# Voltage_regulator_board.net
KiCad netlist of a schematic drawn in EAGLE
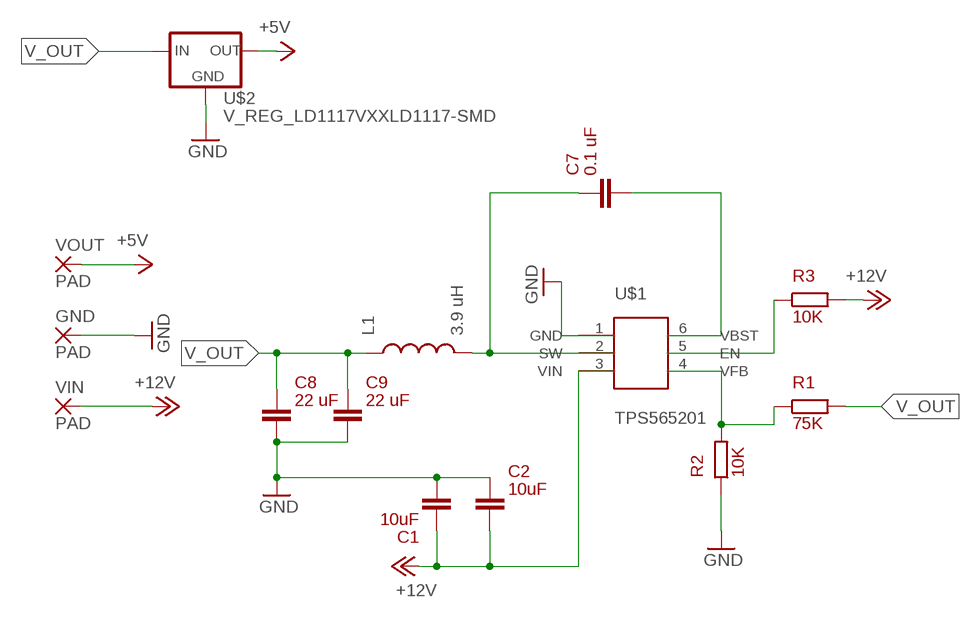
[diagram p0: schematic, sheet 1]

(export (version "E")
  (design (tool "Eeschema 10.0.6"))
  (components
    (comp (ref "C1")
      (value "10uF")
      (footprint "eagle-import:C1206K")
      (libsource (lib "eagle-import") (part "1206CAPACITOR"))
    )
    (comp (ref "C2")
      (value "10uF")
      (footprint "eagle-import:C1206K")
      (libsource (lib "eagle-import") (part "1206CAPACITOR"))
    )
    (comp (ref "C7")
      (value "0.1 uF")
      (footprint "eagle-import:C1206K")
      (libsource (lib "eagle-import") (part "1206CAPACITOR"))
    )
    (comp (ref "C8")
      (value "22 uF")
      (footprint "eagle-import:C1206K")
      (libsource (lib "eagle-import") (part "1206CAPACITOR"))
    )
    (comp (ref "C9")
      (value "22 uF")
      (footprint "eagle-import:C1206K")
      (libsource (lib "eagle-import") (part "1206CAPACITOR"))
    )
    (comp (ref "GND")
      (value "PAD")
      (footprint "eagle-import:PAD")
      (libsource (lib "eagle-import") (part "PAD"))
    )
    (comp (ref "L1")
      (value "3.9 uH")
      (footprint "eagle-import:SRN6028")
      (libsource (lib "eagle-import") (part "SRN6028"))
    )
    (comp (ref "R1")
      (value "75K")
      (footprint "eagle-import:C0603K")
      (libsource (lib "eagle-import") (part "0603RESISTOR"))
    )
    (comp (ref "R2")
      (value "10K")
      (footprint "eagle-import:C0603K")
      (libsource (lib "eagle-import") (part "0603RESISTOR"))
    )
    (comp (ref "R3")
      (value "10K")
      (footprint "eagle-import:C0603K")
      (libsource (lib "eagle-import") (part "0603RESISTOR"))
    )
    (comp (ref "U$1")
      (value "TPS565201")
      (footprint "eagle-import:SOT23-6")
      (libsource (lib "eagle-import") (part "TPS565201"))
    )
    (comp (ref "U$2")
      (value "V_REG_LD1117VXXLD1117-SMD")
      (footprint "eagle-import:SOT223")
      (libsource (lib "eagle-import") (part "V_REG_LD1117VXXLD1117-SMD"))
    )
    (comp (ref "VIN")
      (value "PAD")
      (footprint "eagle-import:PAD")
      (libsource (lib "eagle-import") (part "PAD"))
    )
    (comp (ref "VOUT")
      (value "PAD")
      (footprint "eagle-import:PAD")
      (libsource (lib "eagle-import") (part "PAD"))
    )
  )
  (nets
    (net (code "1") (name "+5V") (class "Default")
      (node (ref "U$2") (pin "2") (pinfunction "OUT_2") (pintype "passive"))
      (node (ref "VOUT") (pin "1") (pinfunction "P_1") (pintype "passive"))
    )
    (net (code "2") (name "+12V") (class "Default")
      (node (ref "C1") (pin "1") (pinfunction "1_1") (pintype "passive"))
      (node (ref "C2") (pin "2") (pinfunction "2_2") (pintype "passive"))
      (node (ref "R3") (pin "2") (pinfunction "2_2") (pintype "passive"))
      (node (ref "U$1") (pin "3") (pinfunction "VIN_3") (pintype "bidirectional"))
      (node (ref "VIN") (pin "1") (pinfunction "P_1") (pintype "passive"))
    )
    (net (code "3") (name "GND") (class "Default")
      (node (ref "C1") (pin "2") (pinfunction "2_2") (pintype "passive"))
      (node (ref "C2") (pin "1") (pinfunction "1_1") (pintype "passive"))
      (node (ref "C8") (pin "2") (pinfunction "2_2") (pintype "passive"))
      (node (ref "C9") (pin "2") (pinfunction "2_2") (pintype "passive"))
      (node (ref "GND") (pin "1") (pinfunction "P_1") (pintype "passive"))
      (node (ref "R2") (pin "1") (pinfunction "1_1") (pintype "passive"))
      (node (ref "U$1") (pin "1") (pinfunction "GND_1") (pintype "bidirectional"))
      (node (ref "U$2") (pin "1") (pinfunction "GND_1") (pintype "input"))
    )
    (net (code "4") (name "Net-(L1-2)") (class "Default")
      (node (ref "C7") (pin "1") (pinfunction "1_1") (pintype "passive"))
      (node (ref "L1") (pin "P$2") (pinfunction "2_P$2") (pintype "passive"))
      (node (ref "U$1") (pin "2") (pinfunction "SW_2") (pintype "bidirectional"))
    )
    (net (code "5") (name "Net-(U$1-EN)") (class "Default")
      (node (ref "R3") (pin "1") (pinfunction "1_1") (pintype "passive"))
      (node (ref "U$1") (pin "5") (pinfunction "EN_5") (pintype "bidirectional"))
    )
    (net (code "6") (name "Net-(U$1-VBST)") (class "Default")
      (node (ref "C7") (pin "2") (pinfunction "2_2") (pintype "passive"))
      (node (ref "U$1") (pin "6") (pinfunction "VBST_6") (pintype "bidirectional"))
    )
    (net (code "7") (name "Net-(U$1-VFB)") (class "Default")
      (node (ref "R1") (pin "1") (pinfunction "1_1") (pintype "passive"))
      (node (ref "R2") (pin "2") (pinfunction "2_2") (pintype "passive"))
      (node (ref "U$1") (pin "4") (pinfunction "VFB_4") (pintype "bidirectional"))
    )
    (net (code "8") (name "V_OUT") (class "Default")
      (node (ref "C8") (pin "1") (pinfunction "1_1") (pintype "passive"))
      (node (ref "C9") (pin "1") (pinfunction "1_1") (pintype "passive"))
      (node (ref "L1") (pin "P$1") (pinfunction "1_P$1") (pintype "passive"))
      (node (ref "R1") (pin "2") (pinfunction "2_2") (pintype "passive"))
      (node (ref "U$2") (pin "3") (pinfunction "IN_3") (pintype "input"))
    )
  )
)
